# Final_7.net
KiCad netlist of a schematic drawn in EAGLE
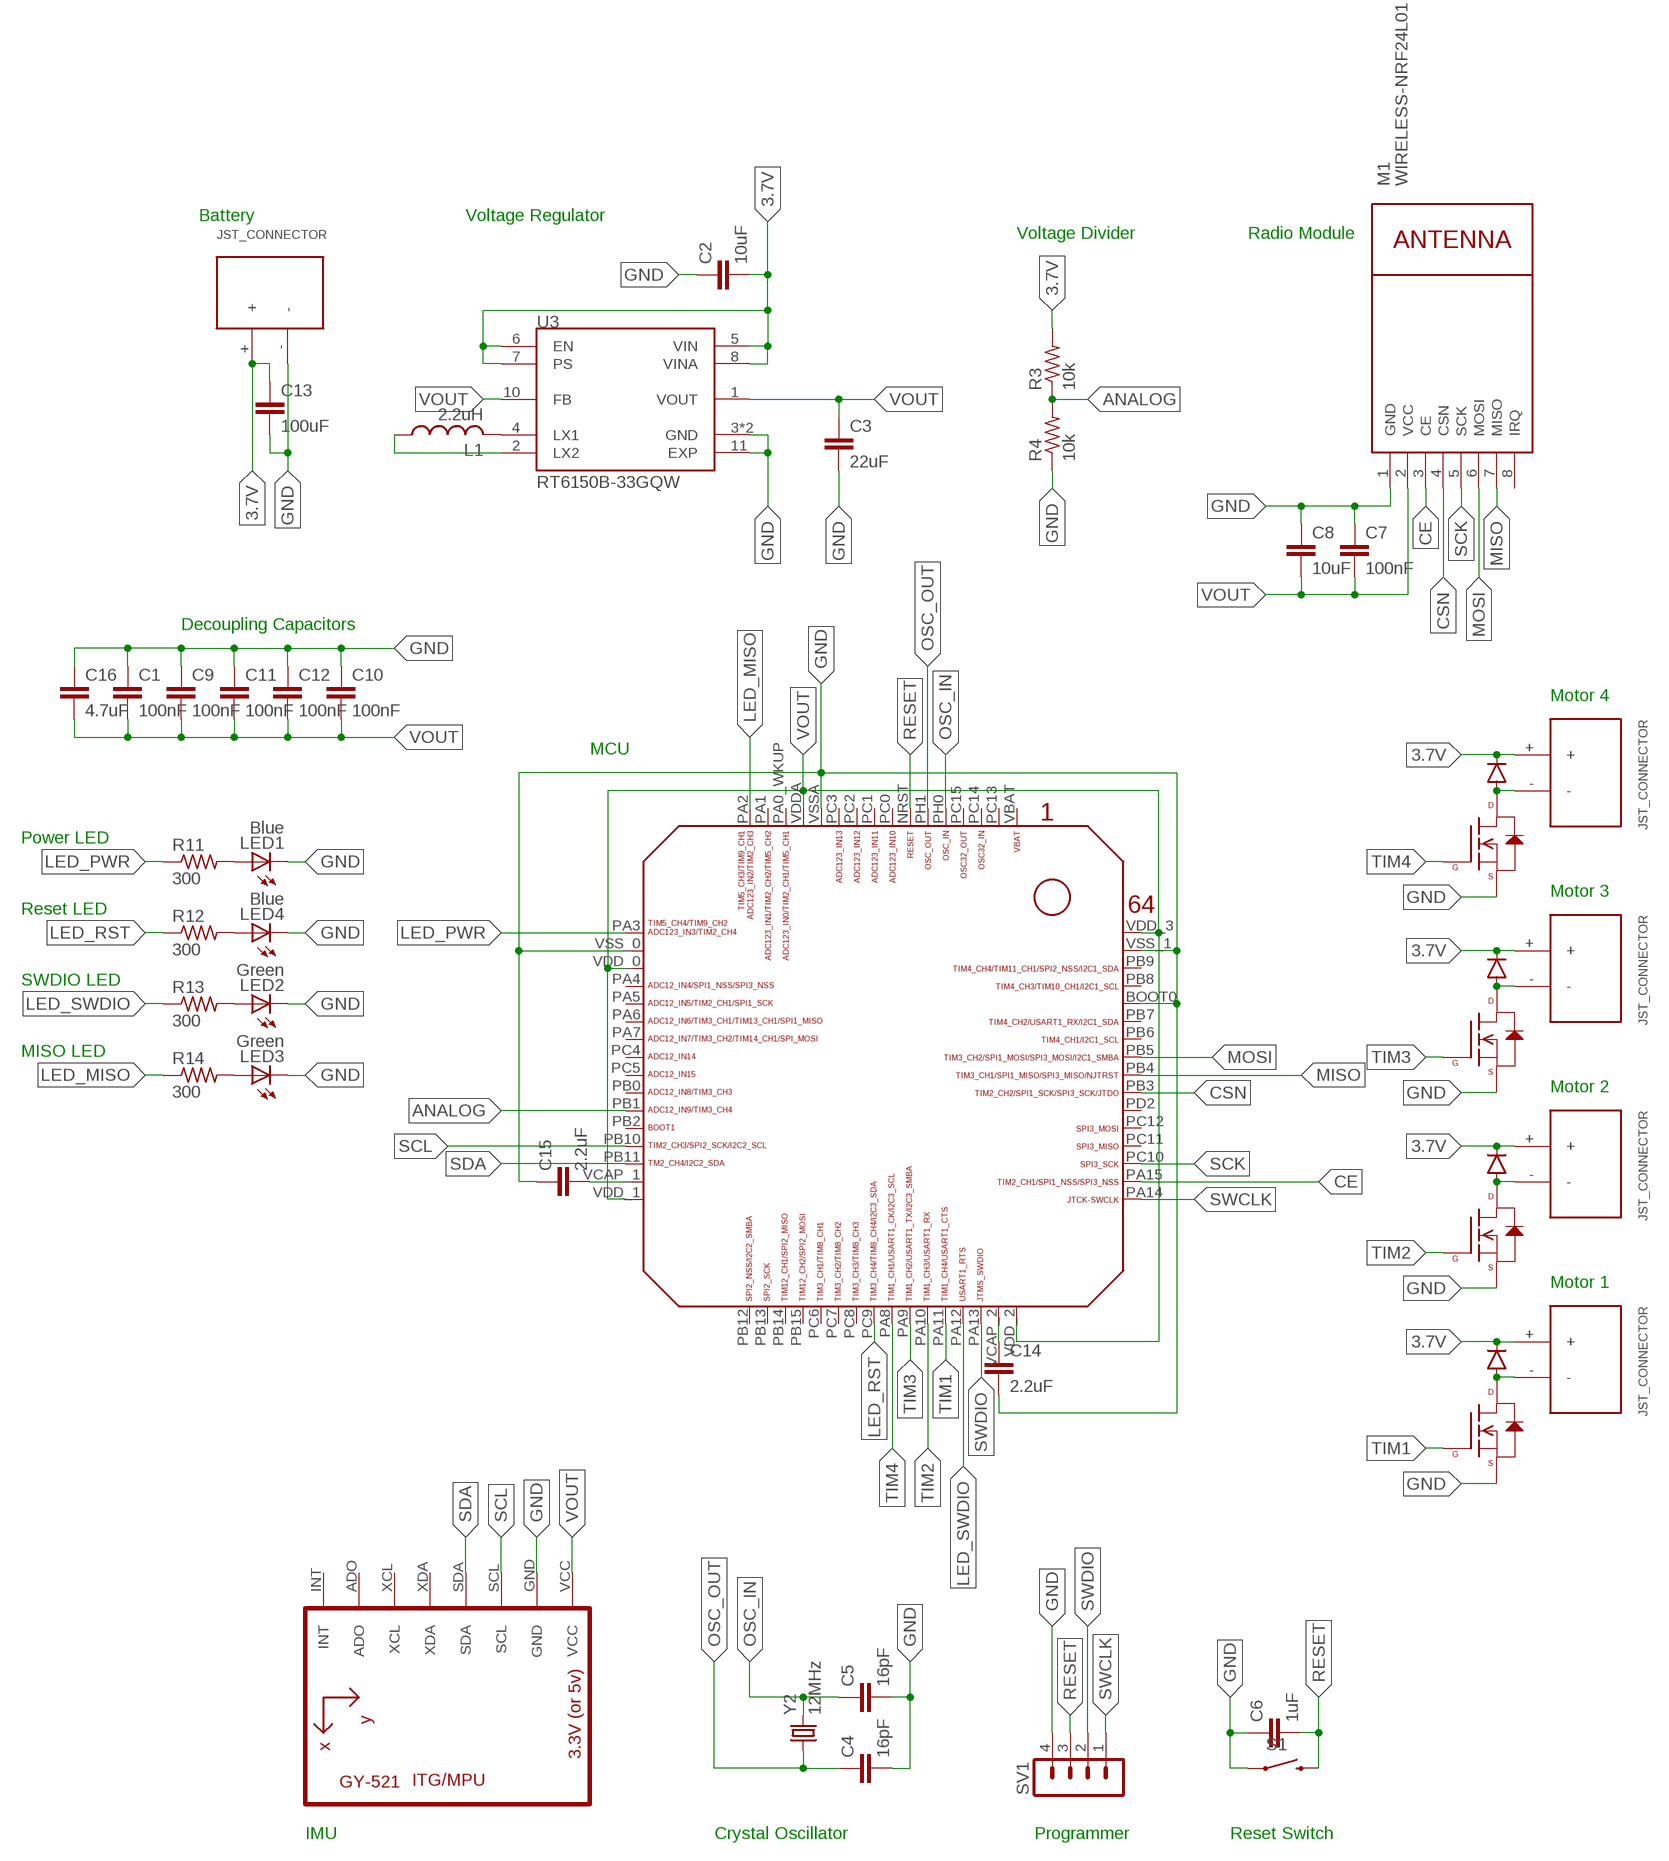
[diagram p0: schematic, sheet 1]

(export (version "E")
  (design (tool "Eeschema 10.0.6"))
  (components
    (comp (ref "C1")
      (value "100nF")
      (footprint "eagle-import:C0603")
      (libsource (lib "eagle-import") (part "rcl_334_C-EUC0603"))
    )
    (comp (ref "C2")
      (value "10uF")
      (footprint "eagle-import:C0603")
      (libsource (lib "eagle-import") (part "rcl_334_C-EUC0603"))
    )
    (comp (ref "C3")
      (value "22uF")
      (footprint "eagle-import:C0603")
      (libsource (lib "eagle-import") (part "rcl_334_C-EUC0603"))
    )
    (comp (ref "C4")
      (value "16pF")
      (footprint "eagle-import:C0603")
      (libsource (lib "eagle-import") (part "rcl_334_C-EUC0603"))
    )
    (comp (ref "C5")
      (value "16pF")
      (footprint "eagle-import:C0603")
      (libsource (lib "eagle-import") (part "rcl_334_C-EUC0603"))
    )
    (comp (ref "C6")
      (value "1uF")
      (footprint "eagle-import:C0603")
      (libsource (lib "eagle-import") (part "rcl_334_C-EUC0603"))
    )
    (comp (ref "C7")
      (value "100nF")
      (footprint "eagle-import:C0603")
      (libsource (lib "eagle-import") (part "rcl_334_C-EUC0603"))
    )
    (comp (ref "C8")
      (value "10uF")
      (footprint "eagle-import:C0603")
      (libsource (lib "eagle-import") (part "rcl_334_C-EUC0603"))
    )
    (comp (ref "C9")
      (value "100nF")
      (footprint "eagle-import:C0603")
      (libsource (lib "eagle-import") (part "rcl_334_C-EUC0603"))
    )
    (comp (ref "C10")
      (value "100nF")
      (footprint "eagle-import:C0603")
      (libsource (lib "eagle-import") (part "rcl_334_C-EUC0603"))
    )
    (comp (ref "C11")
      (value "100nF")
      (footprint "eagle-import:C0603")
      (libsource (lib "eagle-import") (part "rcl_334_C-EUC0603"))
    )
    (comp (ref "C12")
      (value "100nF")
      (footprint "eagle-import:C0603")
      (libsource (lib "eagle-import") (part "rcl_334_C-EUC0603"))
    )
    (comp (ref "C13")
      (value "100uF")
      (footprint "eagle-import:C1206")
      (libsource (lib "eagle-import") (part "rcl_334_C-EUC1206"))
    )
    (comp (ref "C14")
      (value "2.2uF")
      (footprint "eagle-import:C0603")
      (libsource (lib "eagle-import") (part "C-EUC0603"))
    )
    (comp (ref "C15")
      (value "2.2uF")
      (footprint "eagle-import:C0603")
      (libsource (lib "eagle-import") (part "C-EUC0603"))
    )
    (comp (ref "C16")
      (value "4.7uF")
      (footprint "eagle-import:C0603")
      (libsource (lib "eagle-import") (part "rcl_334_C-EUC0603"))
    )
    (comp (ref "L1")
      (value "2.2uH")
      (footprint "eagle-import:L0603")
      (libsource (lib "eagle-import") (part "L-USL0603"))
    )
    (comp (ref "LED1")
      (value "Blue")
      (footprint "eagle-import:CHIP-LED0603")
      (libsource (lib "eagle-import") (part "LEDCHIP-LED0603"))
    )
    (comp (ref "LED2")
      (value "Green")
      (footprint "eagle-import:CHIP-LED0603")
      (libsource (lib "eagle-import") (part "LEDCHIP-LED0603"))
    )
    (comp (ref "LED3")
      (value "Green")
      (footprint "eagle-import:CHIP-LED0603")
      (libsource (lib "eagle-import") (part "LEDCHIP-LED0603"))
    )
    (comp (ref "LED4")
      (value "Blue")
      (footprint "eagle-import:CHIP-LED0603")
      (libsource (lib "eagle-import") (part "LEDCHIP-LED0603"))
    )
    (comp (ref "M1")
      (value "WIRELESS-NRF24L01")
      (footprint "eagle-import:WIRELESS-NRF24L01")
      (libsource (lib "eagle-import") (part "WIRELESS-NRF24L01"))
    )
    (comp (ref "R3")
      (value "10k")
      (footprint "eagle-import:R0603")
      (libsource (lib "eagle-import") (part "R-US_R0603"))
    )
    (comp (ref "R4")
      (value "10k")
      (footprint "eagle-import:R0603")
      (libsource (lib "eagle-import") (part "R-US_R0603"))
    )
    (comp (ref "R11")
      (value "300")
      (footprint "eagle-import:R0603")
      (libsource (lib "eagle-import") (part "R-US_R0603"))
    )
    (comp (ref "R12")
      (value "300")
      (footprint "eagle-import:R0603")
      (libsource (lib "eagle-import") (part "R-US_R0603"))
    )
    (comp (ref "R13")
      (value "300")
      (footprint "eagle-import:R0603")
      (libsource (lib "eagle-import") (part "R-US_R0603"))
    )
    (comp (ref "R14")
      (value "300")
      (footprint "eagle-import:R0603")
      (libsource (lib "eagle-import") (part "R-US_R0603"))
    )
    (comp (ref "S1")
      (value "SWITCH-MOMENTARY-2SMD")
      (footprint "eagle-import:TACTILE-SWITCH-SMD")
      (libsource (lib "eagle-import") (part "SWITCH-MOMENTARY-2SMD"))
    )
    (comp (ref "SV1")
      (value "MA04-1")
      (footprint "eagle-import:MA04-1")
      (libsource (lib "eagle-import") (part "MA04-1"))
    )
    (comp (ref "U$1")
      (value "STM32F405/415_LQFP64")
      (footprint "eagle-import:STM32F405_415_LQFP64")
      (libsource (lib "eagle-import") (part "STM32F405/415_LQFP64"))
    )
    (comp (ref "U$2")
      (value "JST_CONNECTOR_FEMALE")
      (footprint "eagle-import:JST_CONNECTOR_FEMALE")
      (libsource (lib "eagle-import") (part "JST_CONNECTOR_FEMALE"))
    )
    (comp (ref "U$3")
      (value "JST_CONNECTOR_FEMALE")
      (footprint "eagle-import:JST_CONNECTOR_FEMALE")
      (libsource (lib "eagle-import") (part "JST_CONNECTOR_FEMALE"))
    )
    (comp (ref "U$4")
      (value "JST_CONNECTOR_FEMALE")
      (footprint "eagle-import:JST_CONNECTOR_FEMALE")
      (libsource (lib "eagle-import") (part "JST_CONNECTOR_FEMALE"))
    )
    (comp (ref "U$5")
      (value "JST_CONNECTOR_FEMALE")
      (footprint "eagle-import:JST_CONNECTOR_FEMALE")
      (libsource (lib "eagle-import") (part "JST_CONNECTOR_FEMALE"))
    )
    (comp (ref "U$6")
      (value "JST_CONNECTOR_FEMALE")
      (footprint "eagle-import:JST_CONNECTOR_FEMALE")
      (libsource (lib "eagle-import") (part "JST_CONNECTOR_FEMALE"))
    )
    (comp (ref "U$7")
      (value "N-CHANNEL-MOSFET-IRLML6244TRPBF")
      (footprint "eagle-import:SOT23-3")
      (libsource (lib "eagle-import") (part "N-CHANNEL-MOSFET-IRLML6244TRPBF"))
    )
    (comp (ref "U$8")
      (value "N-CHANNEL-MOSFET-IRLML6244TRPBF")
      (footprint "eagle-import:SOT23-3")
      (libsource (lib "eagle-import") (part "N-CHANNEL-MOSFET-IRLML6244TRPBF"))
    )
    (comp (ref "U$9")
      (value "N-CHANNEL-MOSFET-IRLML6244TRPBF")
      (footprint "eagle-import:SOT23-3")
      (libsource (lib "eagle-import") (part "N-CHANNEL-MOSFET-IRLML6244TRPBF"))
    )
    (comp (ref "U$10")
      (value "N-CHANNEL-MOSFET-IRLML6244TRPBF")
      (footprint "eagle-import:SOT23-3")
      (libsource (lib "eagle-import") (part "N-CHANNEL-MOSFET-IRLML6244TRPBF"))
    )
    (comp (ref "U$11")
      (value "DB2W40300L")
      (footprint "eagle-import:MINI2-F3-B")
      (libsource (lib "eagle-import") (part "DB2W40300L"))
    )
    (comp (ref "U$12")
      (value "DB2W40300L")
      (footprint "eagle-import:MINI2-F3-B")
      (libsource (lib "eagle-import") (part "DB2W40300L"))
    )
    (comp (ref "U$13")
      (value "DB2W40300L")
      (footprint "eagle-import:MINI2-F3-B")
      (libsource (lib "eagle-import") (part "DB2W40300L"))
    )
    (comp (ref "U$14")
      (value "DB2W40300L")
      (footprint "eagle-import:MINI2-F3-B")
      (libsource (lib "eagle-import") (part "DB2W40300L"))
    )
    (comp (ref "U2")
      (value "GY-521MPU6050")
      (footprint "eagle-import:GY-521")
      (libsource (lib "eagle-import") (part "GY-521MPU6050"))
    )
    (comp (ref "U3")
      (value "RT6150B-33GQW")
      (footprint "eagle-import:SON50P250X250X80-11N")
      (fields (field (name "DIGI-KEY_PART_NUMBER") "RT6150B-33GQWCT-ND") (field (name "MF") "Richtek USA"))
      (libsource (lib "eagle-import") (part "RT6150B-33GQW"))
    )
    (comp (ref "Y2")
      (value "12MHz")
      (footprint "eagle-import:HC49UP")
      (libsource (lib "eagle-import") (part "CRYSTALSMD"))
    )
  )
  (nets
    (net (code "1") (name "3.7V") (class "Default")
      (node (ref "C13") (pin "1") (pinfunction "1_1") (pintype "passive"))
      (node (ref "C2") (pin "2") (pinfunction "2_2") (pintype "passive"))
      (node (ref "R3") (pin "2") (pinfunction "2_2") (pintype "passive"))
      (node (ref "U$11") (pin "NEG") (pinfunction "GPIN_NEG") (pintype "passive"))
      (node (ref "U$12") (pin "NEG") (pinfunction "GPIN_NEG") (pintype "passive"))
      (node (ref "U$13") (pin "NEG") (pinfunction "GPIN_NEG") (pintype "passive"))
      (node (ref "U$14") (pin "NEG") (pinfunction "GPIN_NEG") (pintype "passive"))
      (node (ref "U$2") (pin "+") (pinfunction "+_+") (pintype "bidirectional"))
      (node (ref "U$3") (pin "+") (pinfunction "+_+") (pintype "bidirectional"))
      (node (ref "U$4") (pin "+") (pinfunction "+_+") (pintype "bidirectional"))
      (node (ref "U$5") (pin "+") (pinfunction "+_+") (pintype "bidirectional"))
      (node (ref "U$6") (pin "+") (pinfunction "+_+") (pintype "bidirectional"))
      (node (ref "U3") (pin "5") (pinfunction "VIN_5") (pintype "power_in"))
      (node (ref "U3") (pin "6") (pinfunction "EN_6") (pintype "input"))
      (node (ref "U3") (pin "7") (pinfunction "PS_7") (pintype "input"))
      (node (ref "U3") (pin "8") (pinfunction "VINA_8") (pintype "power_in"))
    )
    (net (code "2") (name "ANALOG") (class "Default")
      (node (ref "R3") (pin "1") (pinfunction "1_1") (pintype "passive"))
      (node (ref "R4") (pin "2") (pinfunction "2_2") (pintype "passive"))
      (node (ref "U$1") (pin "PB1") (pinfunction "PB1_PB1") (pintype "bidirectional"))
    )
    (net (code "3") (name "CE") (class "Default")
      (node (ref "M1") (pin "3") (pinfunction "CE_3") (pintype "bidirectional"))
      (node (ref "U$1") (pin "PA15") (pinfunction "PA15_PA15") (pintype "bidirectional"))
    )
    (net (code "4") (name "CSN") (class "Default")
      (node (ref "M1") (pin "4") (pinfunction "CSN_4") (pintype "bidirectional"))
      (node (ref "U$1") (pin "PB3") (pinfunction "PB3_PB3") (pintype "bidirectional"))
    )
    (net (code "5") (name "GND") (class "Default")
      (node (ref "C1") (pin "1") (pinfunction "1_1") (pintype "passive"))
      (node (ref "C10") (pin "1") (pinfunction "1_1") (pintype "passive"))
      (node (ref "C11") (pin "1") (pinfunction "1_1") (pintype "passive"))
      (node (ref "C12") (pin "1") (pinfunction "1_1") (pintype "passive"))
      (node (ref "C13") (pin "2") (pinfunction "2_2") (pintype "passive"))
      (node (ref "C14") (pin "2") (pinfunction "2_2") (pintype "passive"))
      (node (ref "C15") (pin "1") (pinfunction "1_1") (pintype "passive"))
      (node (ref "C16") (pin "1") (pinfunction "1_1") (pintype "passive"))
      (node (ref "C2") (pin "1") (pinfunction "1_1") (pintype "passive"))
      (node (ref "C3") (pin "2") (pinfunction "2_2") (pintype "passive"))
      (node (ref "C4") (pin "2") (pinfunction "2_2") (pintype "passive"))
      (node (ref "C5") (pin "2") (pinfunction "2_2") (pintype "passive"))
      (node (ref "C6") (pin "1") (pinfunction "1_1") (pintype "passive"))
      (node (ref "C7") (pin "1") (pinfunction "1_1") (pintype "passive"))
      (node (ref "C8") (pin "1") (pinfunction "1_1") (pintype "passive"))
      (node (ref "C9") (pin "1") (pinfunction "1_1") (pintype "passive"))
      (node (ref "LED1") (pin "C") (pinfunction "C_C") (pintype "passive"))
      (node (ref "LED2") (pin "C") (pinfunction "C_C") (pintype "passive"))
      (node (ref "LED3") (pin "C") (pinfunction "C_C") (pintype "passive"))
      (node (ref "LED4") (pin "C") (pinfunction "C_C") (pintype "passive"))
      (node (ref "M1") (pin "1") (pinfunction "GND_1") (pintype "power_in"))
      (node (ref "R4") (pin "1") (pinfunction "1_1") (pintype "passive"))
      (node (ref "S1") (pin "1") (pinfunction "1_1") (pintype "passive"))
      (node (ref "SV1") (pin "4") (pinfunction "4_4") (pintype "passive"))
      (node (ref "U$1") (pin "BOOT0") (pinfunction "BOOT0_BOOT0") (pintype "bidirectional"))
      (node (ref "U$1") (pin "VSSA") (pinfunction "VSSA_VSSA") (pintype "bidirectional"))
      (node (ref "U$1") (pin "VSS_0") (pinfunction "VSS_0_VSS_0") (pintype "bidirectional"))
      (node (ref "U$1") (pin "VSS_1") (pinfunction "VSS_1_VSS_1") (pintype "bidirectional"))
      (node (ref "U$10") (pin "2") (pinfunction "S_2") (pintype "passive"))
      (node (ref "U$2") (pin "-") (pinfunction "-_-") (pintype "bidirectional"))
      (node (ref "U$7") (pin "2") (pinfunction "S_2") (pintype "passive"))
      (node (ref "U$8") (pin "2") (pinfunction "S_2") (pintype "passive"))
      (node (ref "U$9") (pin "2") (pinfunction "S_2") (pintype "passive"))
      (node (ref "U2") (pin "GND") (pinfunction "GND_GND") (pintype "bidirectional"))
      (node (ref "U3") (pin "11") (pinfunction "EXP_11") (pintype "passive"))
      (node (ref "U3") (pin "3") (pinfunction "GND_3") (pintype "power_in"))
      (node (ref "U3") (pin "9") (pinfunction "GND_9") (pintype "power_in"))
    )
    (net (code "6") (name "LED_MISO") (class "Default")
      (node (ref "R14") (pin "1") (pinfunction "1_1") (pintype "passive"))
      (node (ref "U$1") (pin "PA2") (pinfunction "PA2_PA2") (pintype "bidirectional"))
    )
    (net (code "7") (name "LED_PWR") (class "Default")
      (node (ref "R11") (pin "1") (pinfunction "1_1") (pintype "passive"))
      (node (ref "U$1") (pin "PA3") (pinfunction "PA3_PA3") (pintype "bidirectional"))
    )
    (net (code "8") (name "LED_RST") (class "Default")
      (node (ref "R12") (pin "1") (pinfunction "1_1") (pintype "passive"))
      (node (ref "U$1") (pin "PC9") (pinfunction "PC9_PC9") (pintype "bidirectional"))
    )
    (net (code "9") (name "LED_SWDIO") (class "Default")
      (node (ref "R13") (pin "1") (pinfunction "1_1") (pintype "passive"))
      (node (ref "U$1") (pin "PA12") (pinfunction "PA12_PA12") (pintype "bidirectional"))
    )
    (net (code "10") (name "MISO") (class "Default")
      (node (ref "M1") (pin "7") (pinfunction "MISO_7") (pintype "bidirectional"))
      (node (ref "U$1") (pin "PB4") (pinfunction "PB4_PB4") (pintype "bidirectional"))
    )
    (net (code "11") (name "MOSI") (class "Default")
      (node (ref "M1") (pin "6") (pinfunction "MOSI_6") (pintype "bidirectional"))
      (node (ref "U$1") (pin "PB5") (pinfunction "PB5_PB5") (pintype "bidirectional"))
    )
    (net (code "12") (name "Net-(C14-Pad1)") (class "Default")
      (node (ref "C14") (pin "1") (pinfunction "1_1") (pintype "passive"))
      (node (ref "U$1") (pin "VCAP_2") (pinfunction "VCAP_2_VCAP_2") (pintype "bidirectional"))
    )
    (net (code "13") (name "Net-(C15-Pad2)") (class "Default")
      (node (ref "C15") (pin "2") (pinfunction "2_2") (pintype "passive"))
      (node (ref "U$1") (pin "VCAP_1") (pinfunction "VCAP_1_VCAP_1") (pintype "bidirectional"))
    )
    (net (code "14") (name "Net-(LED1-PadA)") (class "Default")
      (node (ref "LED1") (pin "A") (pinfunction "A_A") (pintype "passive"))
      (node (ref "R11") (pin "2") (pinfunction "2_2") (pintype "passive"))
    )
    (net (code "15") (name "Net-(LED2-PadA)") (class "Default")
      (node (ref "LED2") (pin "A") (pinfunction "A_A") (pintype "passive"))
      (node (ref "R13") (pin "2") (pinfunction "2_2") (pintype "passive"))
    )
    (net (code "16") (name "Net-(LED3-PadA)") (class "Default")
      (node (ref "LED3") (pin "A") (pinfunction "A_A") (pintype "passive"))
      (node (ref "R14") (pin "2") (pinfunction "2_2") (pintype "passive"))
    )
    (net (code "17") (name "Net-(LED4-PadA)") (class "Default")
      (node (ref "LED4") (pin "A") (pinfunction "A_A") (pintype "passive"))
      (node (ref "R12") (pin "2") (pinfunction "2_2") (pintype "passive"))
    )
    (net (code "18") (name "Net-(U$10-D)") (class "Default")
      (node (ref "U$10") (pin "3") (pinfunction "D_3") (pintype "passive"))
      (node (ref "U$14") (pin "POS") (pinfunction "PPIN_POS") (pintype "passive"))
      (node (ref "U$6") (pin "-") (pinfunction "-_-") (pintype "bidirectional"))
    )
    (net (code "19") (name "Net-(U$11-PPIN)") (class "Default")
      (node (ref "U$11") (pin "POS") (pinfunction "PPIN_POS") (pintype "passive"))
      (node (ref "U$3") (pin "-") (pinfunction "-_-") (pintype "bidirectional"))
      (node (ref "U$9") (pin "3") (pinfunction "D_3") (pintype "passive"))
    )
    (net (code "20") (name "Net-(U$12-PPIN)") (class "Default")
      (node (ref "U$12") (pin "POS") (pinfunction "PPIN_POS") (pintype "passive"))
      (node (ref "U$5") (pin "-") (pinfunction "-_-") (pintype "bidirectional"))
      (node (ref "U$8") (pin "3") (pinfunction "D_3") (pintype "passive"))
    )
    (net (code "21") (name "Net-(U$13-PPIN)") (class "Default")
      (node (ref "U$13") (pin "POS") (pinfunction "PPIN_POS") (pintype "passive"))
      (node (ref "U$4") (pin "-") (pinfunction "-_-") (pintype "bidirectional"))
      (node (ref "U$7") (pin "3") (pinfunction "D_3") (pintype "passive"))
    )
    (net (code "22") (name "Net-(U3-LX1)") (class "Default")
      (node (ref "L1") (pin "2") (pinfunction "2_2") (pintype "passive"))
      (node (ref "U3") (pin "4") (pinfunction "LX1_4") (pintype "passive"))
    )
    (net (code "23") (name "Net-(U3-LX2)") (class "Default")
      (node (ref "L1") (pin "1") (pinfunction "1_1") (pintype "passive"))
      (node (ref "U3") (pin "2") (pinfunction "LX2_2") (pintype "passive"))
    )
    (net (code "24") (name "OSC_IN") (class "Default")
      (node (ref "C5") (pin "1") (pinfunction "1_1") (pintype "passive"))
      (node (ref "U$1") (pin "PH0") (pinfunction "PH0_PH0") (pintype "bidirectional"))
      (node (ref "Y2") (pin "2") (pinfunction "2_2") (pintype "passive"))
    )
    (net (code "25") (name "OSC_OUT") (class "Default")
      (node (ref "C4") (pin "1") (pinfunction "1_1") (pintype "passive"))
      (node (ref "U$1") (pin "PH1") (pinfunction "PH1_PH1") (pintype "bidirectional"))
      (node (ref "Y2") (pin "1") (pinfunction "1_1") (pintype "passive"))
    )
    (net (code "26") (name "RESET") (class "Default")
      (node (ref "C6") (pin "2") (pinfunction "2_2") (pintype "passive"))
      (node (ref "S1") (pin "3") (pinfunction "2_3") (pintype "passive"))
      (node (ref "SV1") (pin "3") (pinfunction "3_3") (pintype "passive"))
      (node (ref "U$1") (pin "NRST") (pinfunction "NRST_NRST") (pintype "bidirectional"))
    )
    (net (code "27") (name "SCK") (class "Default")
      (node (ref "M1") (pin "5") (pinfunction "SCK_5") (pintype "bidirectional"))
      (node (ref "U$1") (pin "PC10") (pinfunction "PC10_PC10") (pintype "bidirectional"))
    )
    (net (code "28") (name "SCL") (class "Default")
      (node (ref "U$1") (pin "PB10") (pinfunction "PB10_PB10") (pintype "bidirectional"))
      (node (ref "U2") (pin "SCL") (pinfunction "SCL_SCL") (pintype "bidirectional"))
    )
    (net (code "29") (name "SDA") (class "Default")
      (node (ref "U$1") (pin "PB11") (pinfunction "PB11_PB11") (pintype "bidirectional"))
      (node (ref "U2") (pin "SDA") (pinfunction "SDA_SDA") (pintype "bidirectional"))
    )
    (net (code "30") (name "SWCLK") (class "Default")
      (node (ref "SV1") (pin "1") (pinfunction "1_1") (pintype "passive"))
      (node (ref "U$1") (pin "PA14") (pinfunction "PA14_PA14") (pintype "bidirectional"))
    )
    (net (code "31") (name "SWDIO") (class "Default")
      (node (ref "SV1") (pin "2") (pinfunction "2_2") (pintype "passive"))
      (node (ref "U$1") (pin "PA13") (pinfunction "PA13_PA13") (pintype "bidirectional"))
    )
    (net (code "32") (name "TIM1") (class "Default")
      (node (ref "U$1") (pin "PA11") (pinfunction "PA11_PA11") (pintype "bidirectional"))
      (node (ref "U$10") (pin "1") (pinfunction "G_1") (pintype "passive"))
    )
    (net (code "33") (name "TIM2") (class "Default")
      (node (ref "U$1") (pin "PA10") (pinfunction "PA10_PA10") (pintype "bidirectional"))
      (node (ref "U$8") (pin "1") (pinfunction "G_1") (pintype "passive"))
    )
    (net (code "34") (name "TIM3") (class "Default")
      (node (ref "U$1") (pin "PA9") (pinfunction "PA9_PA9") (pintype "bidirectional"))
      (node (ref "U$7") (pin "1") (pinfunction "G_1") (pintype "passive"))
    )
    (net (code "35") (name "TIM4") (class "Default")
      (node (ref "U$1") (pin "PA8") (pinfunction "PA8_PA8") (pintype "bidirectional"))
      (node (ref "U$9") (pin "1") (pinfunction "G_1") (pintype "passive"))
    )
    (net (code "36") (name "VOUT") (class "Default")
      (node (ref "C1") (pin "2") (pinfunction "2_2") (pintype "passive"))
      (node (ref "C10") (pin "2") (pinfunction "2_2") (pintype "passive"))
      (node (ref "C11") (pin "2") (pinfunction "2_2") (pintype "passive"))
      (node (ref "C12") (pin "2") (pinfunction "2_2") (pintype "passive"))
      (node (ref "C16") (pin "2") (pinfunction "2_2") (pintype "passive"))
      (node (ref "C3") (pin "1") (pinfunction "1_1") (pintype "passive"))
      (node (ref "C7") (pin "2") (pinfunction "2_2") (pintype "passive"))
      (node (ref "C8") (pin "2") (pinfunction "2_2") (pintype "passive"))
      (node (ref "C9") (pin "2") (pinfunction "2_2") (pintype "passive"))
      (node (ref "M1") (pin "2") (pinfunction "VCC_2") (pintype "power_in"))
      (node (ref "U$1") (pin "VDDA") (pinfunction "VDDA_VDDA") (pintype "bidirectional"))
      (node (ref "U$1") (pin "VDD_0") (pinfunction "VDD_0_VDD_0") (pintype "bidirectional"))
      (node (ref "U$1") (pin "VDD_1") (pinfunction "VDD_1_VDD_1") (pintype "bidirectional"))
      (node (ref "U$1") (pin "VDD_2") (pinfunction "VDD_2_VDD_2") (pintype "bidirectional"))
      (node (ref "U$1") (pin "VDD_3") (pinfunction "VDD_3_VDD_3") (pintype "bidirectional"))
      (node (ref "U2") (pin "VCC") (pinfunction "VCC_VCC") (pintype "bidirectional"))
      (node (ref "U3") (pin "1") (pinfunction "VOUT_1") (pintype "output"))
      (node (ref "U3") (pin "10") (pinfunction "FB_10") (pintype "input"))
    )
    (net (code "37") (name "unconnected-(M1-IRQ-Pad8)") (class "Default")
      (node (ref "M1") (pin "8") (pinfunction "IRQ_8") (pintype "bidirectional"))
    )
    (net (code "38") (name "unconnected-(U$1-PA0_AKUP-PadPA0_WKUP)") (class "Default")
      (node (ref "U$1") (pin "PA0_WKUP") (pinfunction "PA0_AKUP_PA0_WKUP") (pintype "bidirectional"))
    )
    (net (code "39") (name "unconnected-(U$1-PadPA1)") (class "Default")
      (node (ref "U$1") (pin "PA1") (pinfunction "PA1_PA1") (pintype "bidirectional"))
    )
    (net (code "40") (name "unconnected-(U$1-PadPA4)") (class "Default")
      (node (ref "U$1") (pin "PA4") (pinfunction "PA4_PA4") (pintype "bidirectional"))
    )
    (net (code "41") (name "unconnected-(U$1-PadPA5)") (class "Default")
      (node (ref "U$1") (pin "PA5") (pinfunction "PA5_PA5") (pintype "bidirectional"))
    )
    (net (code "42") (name "unconnected-(U$1-PadPA6)") (class "Default")
      (node (ref "U$1") (pin "PA6") (pinfunction "PA6_PA6") (pintype "bidirectional"))
    )
    (net (code "43") (name "unconnected-(U$1-PadPA7)") (class "Default")
      (node (ref "U$1") (pin "PA7") (pinfunction "PA7_PA7") (pintype "bidirectional"))
    )
    (net (code "44") (name "unconnected-(U$1-PadPB0)") (class "Default")
      (node (ref "U$1") (pin "PB0") (pinfunction "PB0_PB0") (pintype "bidirectional"))
    )
    (net (code "45") (name "unconnected-(U$1-PadPB2)") (class "Default")
      (node (ref "U$1") (pin "PB2") (pinfunction "PB2_PB2") (pintype "bidirectional"))
    )
    (net (code "46") (name "unconnected-(U$1-PadPB6)") (class "Default")
      (node (ref "U$1") (pin "PB6") (pinfunction "PB6_PB6") (pintype "bidirectional"))
    )
    (net (code "47") (name "unconnected-(U$1-PadPB7)") (class "Default")
      (node (ref "U$1") (pin "PB7") (pinfunction "PB7_PB7") (pintype "bidirectional"))
    )
    (net (code "48") (name "unconnected-(U$1-PadPB8)") (class "Default")
      (node (ref "U$1") (pin "PB8") (pinfunction "PB8_PB8") (pintype "bidirectional"))
    )
    (net (code "49") (name "unconnected-(U$1-PadPB9)") (class "Default")
      (node (ref "U$1") (pin "PB9") (pinfunction "PB9_PB9") (pintype "bidirectional"))
    )
    (net (code "50") (name "unconnected-(U$1-PadPB12)") (class "Default")
      (node (ref "U$1") (pin "PB12") (pinfunction "PB12_PB12") (pintype "bidirectional"))
    )
    (net (code "51") (name "unconnected-(U$1-PadPB13)") (class "Default")
      (node (ref "U$1") (pin "PB13") (pinfunction "PB13_PB13") (pintype "bidirectional"))
    )
    (net (code "52") (name "unconnected-(U$1-PadPB14)") (class "Default")
      (node (ref "U$1") (pin "PB14") (pinfunction "PB14_PB14") (pintype "bidirectional"))
    )
    (net (code "53") (name "unconnected-(U$1-PadPB15)") (class "Default")
      (node (ref "U$1") (pin "PB15") (pinfunction "PB15_PB15") (pintype "bidirectional"))
    )
    (net (code "54") (name "unconnected-(U$1-PadPC0)") (class "Default")
      (node (ref "U$1") (pin "PC0") (pinfunction "PC0_PC0") (pintype "bidirectional"))
    )
    (net (code "55") (name "unconnected-(U$1-PadPC1)") (class "Default")
      (node (ref "U$1") (pin "PC1") (pinfunction "PC1_PC1") (pintype "bidirectional"))
    )
    (net (code "56") (name "unconnected-(U$1-PadPC2)") (class "Default")
      (node (ref "U$1") (pin "PC2") (pinfunction "PC2_PC2") (pintype "bidirectional"))
    )
    (net (code "57") (name "unconnected-(U$1-PadPC3)") (class "Default")
      (node (ref "U$1") (pin "PC3") (pinfunction "PC3_PC3") (pintype "bidirectional"))
    )
    (net (code "58") (name "unconnected-(U$1-PadPC4)") (class "Default")
      (node (ref "U$1") (pin "PC4") (pinfunction "PC4_PC4") (pintype "bidirectional"))
    )
    (net (code "59") (name "unconnected-(U$1-PadPC5)") (class "Default")
      (node (ref "U$1") (pin "PC5") (pinfunction "PC5_PC5") (pintype "bidirectional"))
    )
    (net (code "60") (name "unconnected-(U$1-PadPC6)") (class "Default")
      (node (ref "U$1") (pin "PC6") (pinfunction "PC6_PC6") (pintype "bidirectional"))
    )
    (net (code "61") (name "unconnected-(U$1-PadPC7)") (class "Default")
      (node (ref "U$1") (pin "PC7") (pinfunction "PC7_PC7") (pintype "bidirectional"))
    )
    (net (code "62") (name "unconnected-(U$1-PadPC8)") (class "Default")
      (node (ref "U$1") (pin "PC8") (pinfunction "PC8_PC8") (pintype "bidirectional"))
    )
    (net (code "63") (name "unconnected-(U$1-PadPC11)") (class "Default")
      (node (ref "U$1") (pin "PC11") (pinfunction "PC11_PC11") (pintype "bidirectional"))
    )
    (net (code "64") (name "unconnected-(U$1-PadPC12)") (class "Default")
      (node (ref "U$1") (pin "PC12") (pinfunction "PC12_PC12") (pintype "bidirectional"))
    )
    (net (code "65") (name "unconnected-(U$1-PadPC13)") (class "Default")
      (node (ref "U$1") (pin "PC13") (pinfunction "PC13_PC13") (pintype "bidirectional"))
    )
    (net (code "66") (name "unconnected-(U$1-PadPC14)") (class "Default")
      (node (ref "U$1") (pin "PC14") (pinfunction "PC14_PC14") (pintype "bidirectional"))
    )
    (net (code "67") (name "unconnected-(U$1-PadPC15)") (class "Default")
      (node (ref "U$1") (pin "PC15") (pinfunction "PC15_PC15") (pintype "bidirectional"))
    )
    (net (code "68") (name "unconnected-(U$1-PadPD2)") (class "Default")
      (node (ref "U$1") (pin "PD2") (pinfunction "PD2_PD2") (pintype "bidirectional"))
    )
    (net (code "69") (name "unconnected-(U$1-PadVBAT)") (class "Default")
      (node (ref "U$1") (pin "VBAT") (pinfunction "VBAT_VBAT") (pintype "bidirectional"))
    )
    (net (code "70") (name "unconnected-(U2-PadADO)") (class "Default")
      (node (ref "U2") (pin "ADO") (pinfunction "ADO_ADO") (pintype "bidirectional"))
    )
    (net (code "71") (name "unconnected-(U2-PadINT)") (class "Default")
      (node (ref "U2") (pin "INT") (pinfunction "INT_INT") (pintype "bidirectional"))
    )
    (net (code "72") (name "unconnected-(U2-PadXCL)") (class "Default")
      (node (ref "U2") (pin "XCL") (pinfunction "XCL_XCL") (pintype "bidirectional"))
    )
    (net (code "73") (name "unconnected-(U2-PadXDA)") (class "Default")
      (node (ref "U2") (pin "XDA") (pinfunction "XDA_XDA") (pintype "bidirectional"))
    )
  )
)
